# -_-V1_5.net
KiCad netlist of a schematic drawn in Altium Designer
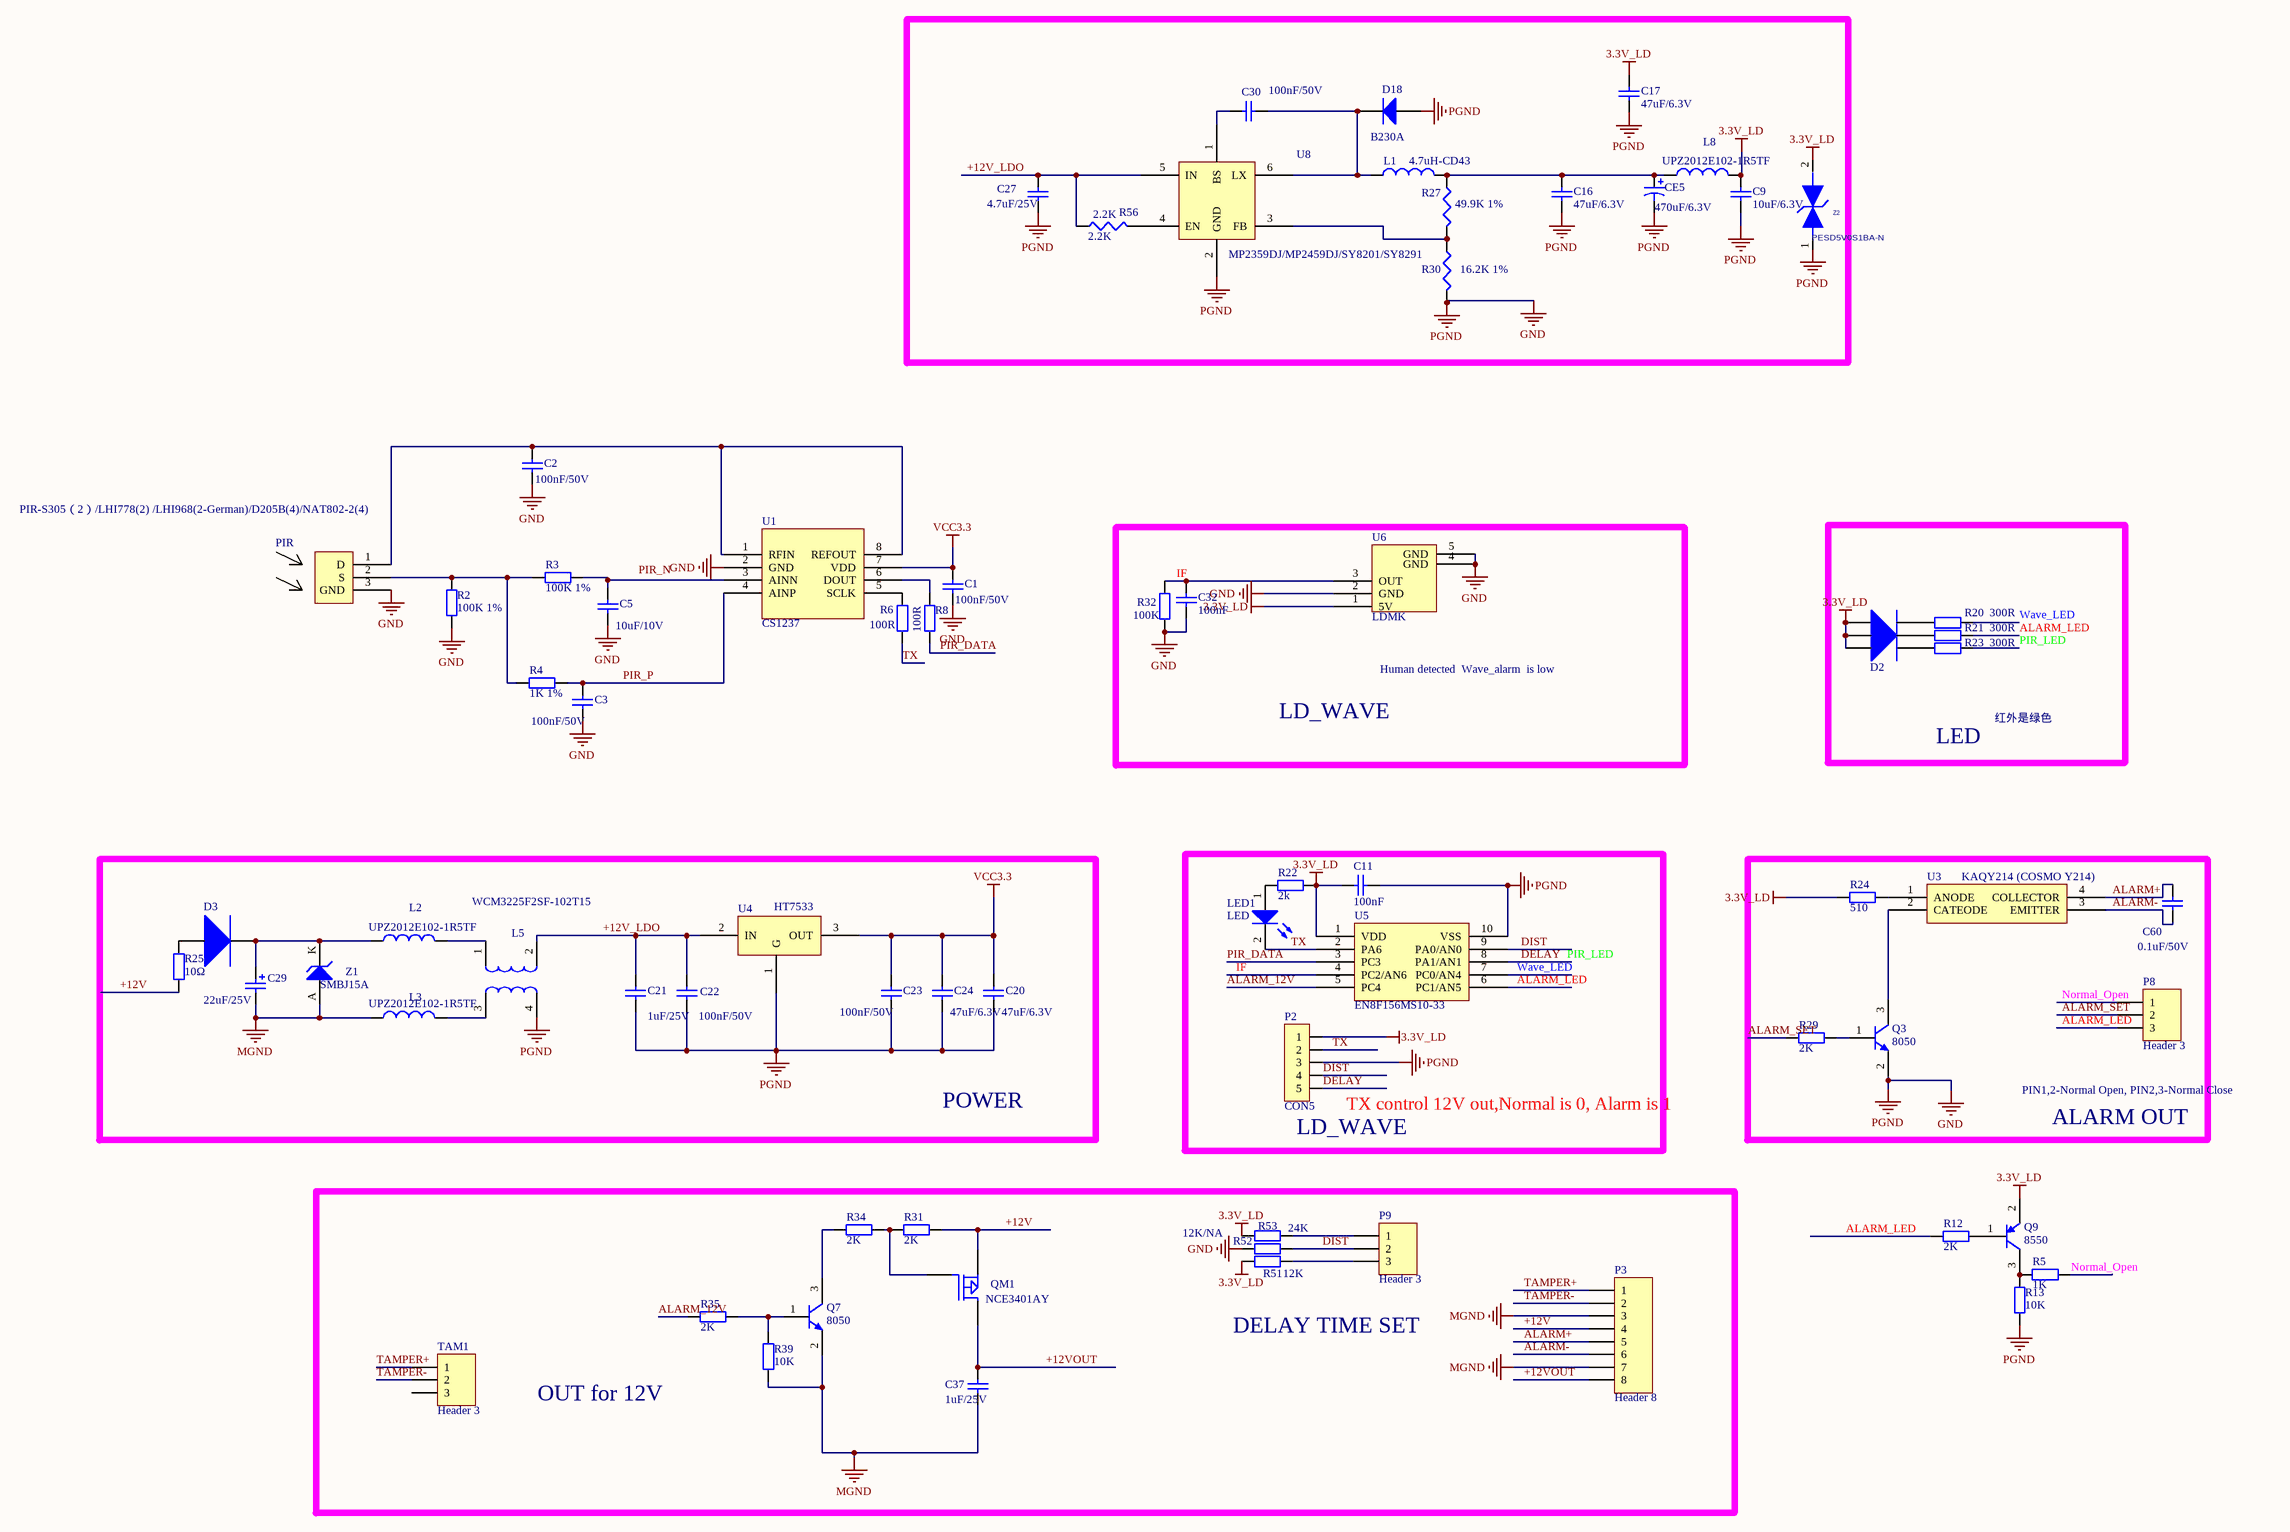
[diagram p0: 美安微波红外-芯海-V1.5.SCHDOC]

(export (version "E")
  (design (tool "Eeschema 10.0.6"))
  (components
    (comp (ref "C1")
      (value "100nF/50V")
      (footprint "0603")
      (description "Capacitor")
      (fields (field (name "PUBLISHER") "Altium Limited"))
      (libsource (lib "Miscellaneous Devices") (part "Cap"))
    )
    (comp (ref "C2")
      (value "100nF/50V")
      (footprint "0603")
      (description "Capacitor")
      (fields (field (name "PUBLISHER") "Altium Limited"))
      (libsource (lib "Miscellaneous Devices") (part "Cap"))
    )
    (comp (ref "C3")
      (value "100nF/50V")
      (footprint "0603")
      (description "Capacitor")
      (fields (field (name "PUBLISHER") "Altium Limited"))
      (libsource (lib "Miscellaneous Devices") (part "Cap"))
    )
    (comp (ref "C5")
      (value "10uF/10V")
      (footprint "C0805")
      (description "Capacitor")
      (fields (field (name "PUBLISHER") "Altium Limited"))
      (libsource (lib "Miscellaneous Devices") (part "Cap"))
    )
    (comp (ref "C9")
      (value "10uF/6.3V")
      (footprint "0603")
      (description "Capacitor")
      (fields (field (name "PUBLISHER") "Altium Limited"))
      (libsource (lib "Miscellaneous Devices") (part "Cap"))
    )
    (comp (ref "C11")
      (value "100nF")
      (footprint "0603")
      (description "Capacitor")
      (fields (field (name "PUBLISHER") "Altium Limited"))
      (libsource (lib "Miscellaneous Devices") (part "Cap"))
    )
    (comp (ref "C16")
      (value "47uF/6.3V")
      (footprint "0805")
      (description "Capacitor (Semiconductor SIM Model)")
      (fields (field (name "PUBLISHER") "Altium Limited"))
      (libsource (lib "Miscellaneous Devices") (part "Cap Semi"))
    )
    (comp (ref "C17")
      (value "47uF/6.3V")
      (footprint "0805")
      (description "Capacitor (Semiconductor SIM Model)")
      (fields (field (name "PUBLISHER") "Altium Limited"))
      (libsource (lib "Miscellaneous Devices") (part "Cap Semi"))
    )
    (comp (ref "C20")
      (value "47uF/6.3V")
      (footprint "C0805")
      (description "Capacitor")
      (fields (field (name "PUBLISHER") "Altium Limited"))
      (libsource (lib "Miscellaneous Devices") (part "Cap"))
    )
    (comp (ref "C21")
      (value "1uF/25V")
      (footprint "C0805")
      (description "Capacitor")
      (fields (field (name "PUBLISHER") "Altium Limited"))
      (libsource (lib "Miscellaneous Devices") (part "Cap"))
    )
    (comp (ref "C22")
      (value "100nF/50V")
      (footprint "C0603")
      (description "Capacitor")
      (fields (field (name "PUBLISHER") "Altium Limited"))
      (libsource (lib "Miscellaneous Devices") (part "Cap"))
    )
    (comp (ref "C23")
      (value "100nF/50V")
      (footprint "C0603")
      (description "Capacitor")
      (fields (field (name "PUBLISHER") "Altium Limited"))
      (libsource (lib "Miscellaneous Devices") (part "Cap"))
    )
    (comp (ref "C24")
      (value "47uF/6.3V")
      (footprint "C0805")
      (description "Capacitor")
      (fields (field (name "PUBLISHER") "Altium Limited"))
      (libsource (lib "Miscellaneous Devices") (part "Cap"))
    )
    (comp (ref "C27")
      (value "4.7uF/25V")
      (footprint "0805")
      (description "Capacitor (Semiconductor SIM Model)")
      (fields (field (name "PUBLISHER") "Altium Limited"))
      (libsource (lib "Miscellaneous Devices") (part "Cap Semi"))
    )
    (comp (ref "C29")
      (value "22uF/25V")
      (footprint "CAP5.0X5.4")
      (description "Polarized Capacitor (Axial)")
      (fields (field (name "PUBLISHER") "Altium Limited"))
      (libsource (lib "Miscellaneous Devices") (part "Cap Pol2"))
    )
    (comp (ref "C30")
      (value "100nF/50V")
      (footprint "0603")
      (description "Capacitor (Semiconductor SIM Model)")
      (fields (field (name "PUBLISHER") "Altium Limited"))
      (libsource (lib "Miscellaneous Devices") (part "Cap Semi"))
    )
    (comp (ref "C32")
      (value "100nF")
      (footprint "0603")
      (description "Capacitor")
      (fields (field (name "PUBLISHER") "Altium Limited"))
      (libsource (lib "Miscellaneous Devices") (part "Cap"))
    )
    (comp (ref "C37")
      (value "1uF/25V")
      (footprint "C0805")
      (description "Capacitor")
      (fields (field (name "PUBLISHER") "Altium Limited"))
      (libsource (lib "Miscellaneous Devices") (part "Cap"))
    )
    (comp (ref "C60")
      (value "0.1uF/50V")
      (footprint "C0603")
      (description "Capacitor")
      (fields (field (name "PUBLISHER") "Altium Limited"))
      (libsource (lib "Miscellaneous Devices") (part "Cap"))
    )
    (comp (ref "CE5")
      (value "470uF/6.3V")
      (footprint "CAP6.3X5.4")
      (description "Polarized Capacitor (Radial)")
      (fields (field (name "PUBLISHER") "Altium Limited"))
      (libsource (lib "Miscellaneous Devices") (part "Cap Pol1"))
    )
    (comp (ref "D2") (value "led三色共阴极灯") (footprint "三色灯") (libsource (lib "微波红外双鉴电路") (part "led三色共阴极灯")))
    (comp (ref "D3") (value "SS14") (footprint "SS14") (libsource (lib "微波红外双鉴电路") (part "SS14")))
    (comp (ref "D18")
      (value "B230A")
      (footprint "SMA")
      (description "1 Amp General Purpose Rectifier")
      (fields (field (name "PUBLISHER") "Altium Limited"))
      (libsource (lib "Miscellaneous Devices") (part "Diode 1N4007"))
    )
    (comp (ref "L1")
      (value "4.7uH-CD43")
      (footprint "CDRH3D16")
      (description "Inductor")
      (fields (field (name "PUBLISHER") "Altium Limited"))
      (libsource (lib "") (part "Inductor_1"))
    )
    (comp (ref "L2")
      (value "UPZ2012E102-1R5TF")
      (footprint "R0805")
      (description "Inductor")
      (fields (field (name "PUBLISHER") "Altium Limited"))
      (libsource (lib "Miscellaneous Devices") (part "Inductor"))
    )
    (comp (ref "L3")
      (value "UPZ2012E102-1R5TF")
      (footprint "R0805")
      (description "Inductor")
      (fields (field (name "PUBLISHER") "Altium Limited"))
      (libsource (lib "Miscellaneous Devices") (part "Inductor"))
    )
    (comp (ref "L5")
      (value "WCM3225F2SF-102T15")
      (footprint "CMC-3225")
      (description "Transformer")
      (fields (field (name "PUBLISHER") "Altium Limited"))
      (libsource (lib "Miscellaneous Devices") (part "Trans"))
    )
    (comp (ref "L8")
      (value "UPZ2012E102-1R5TF")
      (footprint "R0805")
      (description "Inductor")
      (fields (field (name "PUBLISHER") "Altium Limited"))
      (libsource (lib "Miscellaneous Devices") (part "Inductor"))
    )
    (comp (ref "LED1")
      (value "LED")
      (footprint "LED-0603")
      (fields (field (name "PUBLISHER") "Altium Limited"))
      (libsource (lib "Miscellaneous Devices") (part "LED0"))
    )
    (comp (ref "P2")
      (value "CON5")
      (footprint "PH2.0-5P")
      (description "Connector")
      (libsource (lib "*") (part "CON5"))
    )
    (comp (ref "P3")
      (value "Header 8")
      (footprint "5.08dip-8")
      (description "Header, 8-Pin")
      (fields (field (name "PUBLISHER") "Altium Limited"))
      (libsource (lib "Miscellaneous Connectors") (part "Header 8"))
    )
    (comp (ref "P8")
      (value "Header 3")
      (footprint "HDR1X3")
      (description "Header, 3-Pin")
      (fields (field (name "PUBLISHER") "Altium Limited"))
      (libsource (lib "Miscellaneous Connectors") (part "Header 3"))
    )
    (comp (ref "P9")
      (value "Header 3")
      (footprint "HDR1X3")
      (description "Header, 3-Pin")
      (fields (field (name "PUBLISHER") "Altium Limited"))
      (libsource (lib "Miscellaneous Connectors") (part "Header 3"))
    )
    (comp (ref "PIR")
      (value "PIR-S305（2）/LHI778(2) /LHI968(2-German)/D205B(4)/NAT802-2(4)")
      (footprint "pir3")
      (libsource (lib "安防") (part "PIR"))
    )
    (comp (ref "Q3")
      (value "8050")
      (footprint "8050&8550")
      (description "NPN General Purpose Amplifier")
      (fields (field (name "PUBLISHER") "Altium Limited"))
      (libsource (lib "圆形报警器NEW-V2.0") (part "2N3904"))
    )
    (comp (ref "Q7")
      (value "8050")
      (footprint "8050&8550")
      (description "NPN General Purpose Amplifier")
      (fields (field (name "PUBLISHER") "Altium Limited"))
      (libsource (lib "圆形报警器NEW-V2.0") (part "2N3904"))
    )
    (comp (ref "Q9")
      (value "8550")
      (footprint "8050&8550")
      (description "PNP General Purpose Amplifier")
      (fields (field (name "PUBLISHER") "Altium Limited"))
      (libsource (lib "圆形报警器NEW-V2.0") (part "2N3906"))
    )
    (comp (ref "QM1") (value "NCE3401AY") (footprint "SOT-23") (libsource (lib "*") (part "MOSFET P")))
    (comp (ref "R2")
      (value "100K 1%")
      (footprint "R0603")
      (description "Resistor")
      (fields (field (name "PUBLISHER") "Altium Limited"))
      (libsource (lib "Miscellaneous Devices") (part "Res2"))
    )
    (comp (ref "R3")
      (value "100K 1%")
      (footprint "R0603")
      (description "Resistor")
      (fields (field (name "PUBLISHER") "Altium Limited"))
      (libsource (lib "") (part "Res2_3"))
    )
    (comp (ref "R4")
      (value "1K 1%")
      (footprint "R0603")
      (description "Resistor")
      (fields (field (name "PUBLISHER") "Altium Limited"))
      (libsource (lib "") (part "Res2_3"))
    )
    (comp (ref "R5")
      (value "1K")
      (footprint "R0603")
      (description "Resistor")
      (fields (field (name "PUBLISHER") "Altium Limited"))
      (libsource (lib "") (part "Res2_2"))
    )
    (comp (ref "R6")
      (value "100R")
      (footprint "R0603")
      (description "Resistor")
      (fields (field (name "PUBLISHER") "Altium Limited"))
      (libsource (lib "") (part "Res2_1"))
    )
    (comp (ref "R8")
      (value "100R")
      (footprint "R0603")
      (description "Resistor")
      (fields (field (name "PUBLISHER") "Altium Limited"))
      (libsource (lib "") (part "Res2_1"))
    )
    (comp (ref "R12")
      (value "2K")
      (footprint "R0603")
      (description "Resistor")
      (fields (field (name "PUBLISHER") "Altium Limited"))
      (libsource (lib "") (part "Res2_3"))
    )
    (comp (ref "R13")
      (value "10K")
      (footprint "R0603")
      (description "Resistor")
      (fields (field (name "PUBLISHER") "Altium Limited"))
      (libsource (lib "") (part "Res2_1"))
    )
    (comp (ref "R20")
      (value "300R")
      (footprint "R0603")
      (description "Resistor")
      (fields (field (name "Comment") "Res2") (field (name "PUBLISHER") "Altium Limited"))
      (libsource (lib "") (part "Res2_3"))
    )
    (comp (ref "R21")
      (value "300R")
      (footprint "R0603")
      (description "Resistor")
      (fields (field (name "Comment") "Res2") (field (name "PUBLISHER") "Altium Limited"))
      (libsource (lib "") (part "Res2_3"))
    )
    (comp (ref "R22")
      (value "2k")
      (footprint "R0603")
      (description "Resistor")
      (fields (field (name "Comment") "Res2") (field (name "PUBLISHER") "Altium Limited"))
      (libsource (lib "") (part "Res2_3"))
    )
    (comp (ref "R23")
      (value "300R")
      (footprint "R0603")
      (description "Resistor")
      (fields (field (name "Comment") "Res2") (field (name "PUBLISHER") "Altium Limited"))
      (libsource (lib "") (part "Res2_3"))
    )
    (comp (ref "R24")
      (value "510")
      (footprint "R0603")
      (description "Resistor")
      (fields (field (name "PUBLISHER") "Altium Limited"))
      (libsource (lib "") (part "Res2_3"))
    )
    (comp (ref "R25")
      (value "10Ω")
      (footprint "C0805")
      (description "Resistor")
      (fields (field (name "PUBLISHER") "Altium Limited"))
      (libsource (lib "") (part "Res2_1"))
    )
    (comp (ref "R27")
      (value "49.9K 1%")
      (footprint "0603")
      (description "Resistor")
      (fields (field (name "PUBLISHER") "Altium Limited"))
      (libsource (lib "Miscellaneous Devices") (part "Res3"))
    )
    (comp (ref "R29")
      (value "2K")
      (footprint "R0603")
      (description "Resistor")
      (fields (field (name "PUBLISHER") "Altium Limited"))
      (libsource (lib "") (part "Res2_2"))
    )
    (comp (ref "R30")
      (value "16.2K 1%")
      (footprint "0603")
      (description "Resistor")
      (fields (field (name "PUBLISHER") "Altium Limited"))
      (libsource (lib "Miscellaneous Devices") (part "Res3"))
    )
    (comp (ref "R31")
      (value "2K")
      (footprint "R0603")
      (description "Resistor")
      (fields (field (name "PUBLISHER") "Altium Limited"))
      (libsource (lib "") (part "Res2_2"))
    )
    (comp (ref "R32")
      (value "100K")
      (footprint "R0603")
      (description "Resistor")
      (fields (field (name "PUBLISHER") "Altium Limited"))
      (libsource (lib "Miscellaneous Devices") (part "Res2"))
    )
    (comp (ref "R34")
      (value "2K")
      (footprint "R0603")
      (description "Resistor")
      (fields (field (name "PUBLISHER") "Altium Limited"))
      (libsource (lib "") (part "Res2_2"))
    )
    (comp (ref "R35")
      (value "2K")
      (footprint "R0603")
      (description "Resistor")
      (fields (field (name "PUBLISHER") "Altium Limited"))
      (libsource (lib "") (part "Res2_2"))
    )
    (comp (ref "R39")
      (value "10K")
      (footprint "R0603")
      (description "Resistor")
      (fields (field (name "PUBLISHER") "Altium Limited"))
      (libsource (lib "Miscellaneous Devices") (part "Res2"))
    )
    (comp (ref "R51")
      (value "12K")
      (footprint "R0603")
      (description "Resistor")
      (fields (field (name "PUBLISHER") "Altium Limited"))
      (libsource (lib "*") (part "Res2"))
    )
    (comp (ref "R52")
      (value "12K/NA")
      (footprint "R0603")
      (description "Resistor")
      (fields (field (name "PUBLISHER") "Altium Limited"))
      (libsource (lib "*") (part "Res2"))
    )
    (comp (ref "R53")
      (value "24K")
      (footprint "R0603")
      (description "Resistor")
      (fields (field (name "PUBLISHER") "Altium Limited"))
      (libsource (lib "*") (part "Res2"))
    )
    (comp (ref "R56")
      (value "2.2K")
      (footprint "0603")
      (description "Resistor")
      (fields (field (name "ALTIUM_VALUE") "2.2K") (field (name "PUBLISHER") "Altium Limited"))
      (libsource (lib "Miscellaneous Devices") (part "Res3"))
    )
    (comp (ref "TAM1")
      (value "Header 3")
      (footprint "KW12")
      (description "Header, 3-Pin")
      (fields (field (name "PUBLISHER") "Altium Limited"))
      (libsource (lib "Miscellaneous Connectors") (part "Header 3"))
    )
    (comp (ref "U1") (value "CS1237") (footprint "SOP_8") (libsource (lib "美安微波红外-芯海-V0.1") (part "CS1237")))
    (comp (ref "U3")
      (value "KAQY214 (COSMO Y214)")
      (footprint "TLP627")
      (fields (field (name "Comment") "TLP627"))
      (libsource (lib "微波红外双鉴电路") (part "TLP627"))
    )
    (comp (ref "U4") (value "HT7533") (footprint "SOT-89") (libsource (lib "MYLIB") (part "12S33")))
    (comp (ref "U5")
      (value "EN8F156MS10-33")
      (footprint "My Footprint View:MSOP10-0.5")
      (libsource (lib "Schlib1") (part "EN8F156MS10-33"))
    )
    (comp (ref "U6")
      (value "LDMK")
      (footprint "LDMK")
      (libsource (lib "BD-SY-NOPOWER-TS01S-V1.0") (part "LDMK"))
    )
    (comp (ref "U8")
      (value "MP2359DJ/MP2459DJ/SY8201/SY8291")
      (footprint "SOT23-6")
      (libsource (lib "SPECIAL-L-V6.6") (part "SY8120B"))
    )
    (comp (ref "Z1")
      (value "SMBJ15A")
      (footprint "SMB")
      (description "Zener Diode")
      (fields (field (name "PUBLISHER") "Altium Limited"))
      (libsource (lib "Miscellaneous Devices") (part "D Zener"))
    )
    (comp (ref "Z2")
      (value "PESD5V0S1BA-N")
      (footprint "SOD-323")
      (description "VBR=5.780V@1mA;VRWM=3.5V@IRWM=0.5uA;Ct=30pF")
      (fields
        (field (name "MFR") "NXP")
        (field (name "MPN") "RSB6.8CS//VMNZ6.8CST2R  //PESD5V0S1BL//ESDALC6V1-1BM2//ESD9B5.0ST5G//VMNZ6.8CSGJT2R//RSB6.8CM")
      )
      (libsource (lib "*") (part "ESD-PESD5V0S1BL-VMN2"))
    )
  )
  (nets
    (net (code "1") (name "/+12V") (class "Default")
      (node (ref "P3") (pin "4") (pinfunction "4_4") (pintype "passive"))
      (node (ref "QM1") (pin "2") (pinfunction "S_2") (pintype "passive"))
      (node (ref "R25") (pin "2") (pinfunction "2_2") (pintype "passive"))
      (node (ref "R31") (pin "2") (pinfunction "2_2") (pintype "passive"))
    )
    (net (code "2") (name "/+12VOUT") (class "Default")
      (node (ref "C37") (pin "2") (pinfunction "2_2") (pintype "passive"))
      (node (ref "P3") (pin "8") (pinfunction "8_8") (pintype "passive"))
      (node (ref "QM1") (pin "3") (pinfunction "D_3") (pintype "passive"))
    )
    (net (code "3") (name "/+12V_LDO") (class "Default")
      (node (ref "C21") (pin "2") (pinfunction "2_2") (pintype "passive"))
      (node (ref "C22") (pin "2") (pinfunction "2_2") (pintype "passive"))
      (node (ref "C27") (pin "1") (pinfunction "1_1") (pintype "passive"))
      (node (ref "L5") (pin "2") (pinfunction "2_2") (pintype "passive"))
      (node (ref "R56") (pin "1") (pinfunction "1_1") (pintype "passive"))
      (node (ref "U4") (pin "2") (pinfunction "IN_2") (pintype "passive"))
      (node (ref "U8") (pin "5") (pinfunction "IN_5") (pintype "passive"))
    )
    (net (code "4") (name "/ALARM+") (class "Default")
      (node (ref "C60") (pin "2") (pinfunction "2_2") (pintype "passive"))
      (node (ref "P3") (pin "5") (pinfunction "5_5") (pintype "passive"))
      (node (ref "U3") (pin "4") (pinfunction "COLLECTOR_4") (pintype "passive"))
    )
    (net (code "5") (name "/ALARM-") (class "Default")
      (node (ref "C60") (pin "1") (pinfunction "1_1") (pintype "passive"))
      (node (ref "P3") (pin "6") (pinfunction "6_6") (pintype "passive"))
      (node (ref "U3") (pin "3") (pinfunction "EMITTER_3") (pintype "passive"))
    )
    (net (code "6") (name "/ALARM_12V") (class "Default")
      (node (ref "R35") (pin "1") (pinfunction "1_1") (pintype "passive"))
      (node (ref "U5") (pin "5") (pinfunction "PC4_5") (pintype "passive"))
    )
    (net (code "7") (name "/ALARM_LED") (class "Default")
      (node (ref "P8") (pin "3") (pinfunction "3_3") (pintype "passive"))
      (node (ref "R12") (pin "2") (pinfunction "2_2") (pintype "passive"))
      (node (ref "R21") (pin "1") (pinfunction "1_1") (pintype "passive"))
      (node (ref "U5") (pin "6") (pinfunction "PC1/AN5_6") (pintype "passive"))
    )
    (net (code "8") (name "/ALARM_SET") (class "Default")
      (node (ref "P8") (pin "2") (pinfunction "2_2") (pintype "passive"))
      (node (ref "R29") (pin "1") (pinfunction "1_1") (pintype "passive"))
    )
    (net (code "9") (name "/DELAY") (class "Default")
      (node (ref "P2") (pin "5") (pinfunction "5_5") (pintype "passive"))
      (node (ref "R23") (pin "1") (pinfunction "1_1") (pintype "passive"))
      (node (ref "U5") (pin "8") (pinfunction "PA1/AN1_8") (pintype "passive"))
    )
    (net (code "10") (name "/DIST") (class "Default")
      (node (ref "P2") (pin "4") (pinfunction "4_4") (pintype "passive"))
      (node (ref "P9") (pin "2") (pinfunction "2_2") (pintype "passive"))
      (node (ref "R52") (pin "1") (pinfunction "1_1") (pintype "passive"))
      (node (ref "U5") (pin "9") (pinfunction "PA0/AN0_9") (pintype "passive"))
    )
    (net (code "11") (name "/IF") (class "Default")
      (node (ref "C32") (pin "2") (pinfunction "2_2") (pintype "passive"))
      (node (ref "R32") (pin "2") (pinfunction "2_2") (pintype "passive"))
      (node (ref "U5") (pin "4") (pinfunction "PC2/AN6_4") (pintype "passive"))
      (node (ref "U6") (pin "3") (pinfunction "OUT_3") (pintype "passive"))
    )
    (net (code "12") (name "/Normal_Open") (class "Default")
      (node (ref "P8") (pin "1") (pinfunction "1_1") (pintype "passive"))
      (node (ref "R5") (pin "2") (pinfunction "2_2") (pintype "passive"))
    )
    (net (code "13") (name "/PIR_DATA") (class "Default")
      (node (ref "R8") (pin "2") (pinfunction "2_2") (pintype "passive"))
      (node (ref "U5") (pin "3") (pinfunction "PC3_3") (pintype "passive"))
    )
    (net (code "15") (name "/PIR_P") (class "Default")
      (node (ref "C3") (pin "2") (pinfunction "2_2") (pintype "passive"))
      (node (ref "R4") (pin "1") (pinfunction "1_1") (pintype "passive"))
      (node (ref "U1") (pin "4") (pinfunction "AINP_4") (pintype "passive"))
    )
    (net (code "16") (name "/TAMPER+") (class "Default")
      (node (ref "P3") (pin "1") (pinfunction "1_1") (pintype "passive"))
      (node (ref "TAM1") (pin "1") (pinfunction "1_1") (pintype "passive"))
    )
    (net (code "17") (name "/TAMPER-") (class "Default")
      (node (ref "P3") (pin "2") (pinfunction "2_2") (pintype "passive"))
      (node (ref "TAM1") (pin "2") (pinfunction "2_2") (pintype "passive"))
    )
    (net (code "18") (name "/TX") (class "Default")
      (node (ref "LED1") (pin "2") (pinfunction "K_2") (pintype "passive"))
      (node (ref "P2") (pin "2") (pinfunction "2_2") (pintype "passive"))
      (node (ref "R6") (pin "2") (pinfunction "2_2") (pintype "passive"))
      (node (ref "U5") (pin "2") (pinfunction "PA6_2") (pintype "passive"))
    )
    (net (code "20") (name "/Wave_LED") (class "Default")
      (node (ref "R20") (pin "1") (pinfunction "1_1") (pintype "passive"))
      (node (ref "U5") (pin "7") (pinfunction "PC0/AN4_7") (pintype "passive"))
    )
    (net (code "21") (name "3.3V_LD") (class "Default")
      (node (ref "C11") (pin "2") (pinfunction "2_2") (pintype "passive"))
      (node (ref "C17") (pin "1") (pinfunction "1_1") (pintype "passive"))
      (node (ref "C9") (pin "1") (pinfunction "1_1") (pintype "passive"))
      (node (ref "D2") (pin "1") (pinfunction "A+_1") (pintype "passive"))
      (node (ref "D2") (pin "2") (pinfunction "B+_2") (pintype "passive"))
      (node (ref "D2") (pin "3") (pinfunction "C+_3") (pintype "passive"))
      (node (ref "L8") (pin "1") (pinfunction "1_1") (pintype "passive"))
      (node (ref "P2") (pin "1") (pinfunction "1_1") (pintype "passive"))
      (node (ref "Q9") (pin "2") (pinfunction "E_2") (pintype "passive"))
      (node (ref "R22") (pin "1") (pinfunction "1_1") (pintype "passive"))
      (node (ref "R24") (pin "2") (pinfunction "2_2") (pintype "passive"))
      (node (ref "R51") (pin "2") (pinfunction "2_2") (pintype "passive"))
      (node (ref "R53") (pin "2") (pinfunction "2_2") (pintype "passive"))
      (node (ref "U5") (pin "1") (pinfunction "VDD_1") (pintype "passive"))
      (node (ref "U6") (pin "1") (pinfunction "5V_1") (pintype "passive"))
      (node (ref "Z2") (pin "2") (pinfunction "2_2") (pintype "passive"))
    )
    (net (code "22") (name "GND") (class "Default")
      (node (ref "C1") (pin "1") (pinfunction "1_1") (pintype "passive"))
      (node (ref "C11") (pin "1") (pinfunction "1_1") (pintype "passive"))
      (node (ref "C16") (pin "2") (pinfunction "2_2") (pintype "passive"))
      (node (ref "C17") (pin "2") (pinfunction "2_2") (pintype "passive"))
      (node (ref "C2") (pin "1") (pinfunction "1_1") (pintype "passive"))
      (node (ref "C20") (pin "1") (pinfunction "1_1") (pintype "passive"))
      (node (ref "C21") (pin "1") (pinfunction "1_1") (pintype "passive"))
      (node (ref "C22") (pin "1") (pinfunction "1_1") (pintype "passive"))
      (node (ref "C23") (pin "1") (pinfunction "1_1") (pintype "passive"))
      (node (ref "C24") (pin "1") (pinfunction "1_1") (pintype "passive"))
      (node (ref "C27") (pin "2") (pinfunction "2_2") (pintype "passive"))
      (node (ref "C3") (pin "1") (pinfunction "1_1") (pintype "passive"))
      (node (ref "C32") (pin "1") (pinfunction "1_1") (pintype "passive"))
      (node (ref "C5") (pin "1") (pinfunction "1_1") (pintype "passive"))
      (node (ref "C9") (pin "2") (pinfunction "2_2") (pintype "passive"))
      (node (ref "CE5") (pin "2") (pinfunction "2_2") (pintype "passive"))
      (node (ref "D18") (pin "1") (pinfunction "A_1") (pintype "passive"))
      (node (ref "L5") (pin "4") (pinfunction "4_4") (pintype "passive"))
      (node (ref "P2") (pin "3") (pinfunction "3_3") (pintype "passive"))
      (node (ref "PIR") (pin "3") (pinfunction "GND_3") (pintype "passive"))
      (node (ref "Q3") (pin "2") (pinfunction "E_2") (pintype "passive"))
      (node (ref "R13") (pin "2") (pinfunction "2_2") (pintype "passive"))
      (node (ref "R2") (pin "1") (pinfunction "1_1") (pintype "passive"))
      (node (ref "R30") (pin "2") (pinfunction "2_2") (pintype "passive"))
      (node (ref "R32") (pin "1") (pinfunction "1_1") (pintype "passive"))
      (node (ref "R52") (pin "2") (pinfunction "2_2") (pintype "passive"))
      (node (ref "U1") (pin "2") (pinfunction "GND_2") (pintype "passive"))
      (node (ref "U4") (pin "1") (pinfunction "G_1") (pintype "passive"))
      (node (ref "U5") (pin "10") (pinfunction "VSS_10") (pintype "passive"))
      (node (ref "U6") (pin "2") (pinfunction "GND_2") (pintype "passive"))
      (node (ref "U6") (pin "4") (pinfunction "GND_4") (pintype "passive"))
      (node (ref "U6") (pin "5") (pinfunction "GND_5") (pintype "passive"))
      (node (ref "U8") (pin "2") (pinfunction "GND_2") (pintype "passive"))
      (node (ref "Z2") (pin "1") (pinfunction "1_1") (pintype "passive"))
    )
    (net (code "23") (name "MGND") (class "Default")
      (node (ref "C29") (pin "2") (pinfunction "2_2") (pintype "passive"))
      (node (ref "C37") (pin "1") (pinfunction "1_1") (pintype "passive"))
      (node (ref "L3") (pin "2") (pinfunction "2_2") (pintype "passive"))
      (node (ref "P3") (pin "3") (pinfunction "3_3") (pintype "passive"))
      (node (ref "P3") (pin "7") (pinfunction "7_7") (pintype "passive"))
      (node (ref "Q7") (pin "2") (pinfunction "E_2") (pintype "passive"))
      (node (ref "R39") (pin "1") (pinfunction "1_1") (pintype "passive"))
      (node (ref "Z1") (pin "A") (pinfunction "A_A") (pintype "passive"))
    )
    (net (code "24") (name "Net-(C16-Pad1)") (class "Default")
      (node (ref "C16") (pin "1") (pinfunction "1_1") (pintype "passive"))
      (node (ref "CE5") (pin "1") (pinfunction "1_1") (pintype "passive"))
      (node (ref "L1") (pin "2") (pinfunction "2_2") (pintype "passive"))
      (node (ref "L8") (pin "2") (pinfunction "2_2") (pintype "passive"))
      (node (ref "R27") (pin "1") (pinfunction "1_1") (pintype "passive"))
    )
    (net (code "25") (name "Net-(D2-A-)") (class "Default")
      (node (ref "D2") (pin "4") (pinfunction "A-_4") (pintype "passive"))
      (node (ref "R20") (pin "2") (pinfunction "2_2") (pintype "passive"))
    )
    (net (code "26") (name "Net-(D2-B-)") (class "Default")
      (node (ref "D2") (pin "5") (pinfunction "B-_5") (pintype "passive"))
      (node (ref "R21") (pin "2") (pinfunction "2_2") (pintype "passive"))
    )
    (net (code "27") (name "Net-(D2-C-)") (class "Default")
      (node (ref "D2") (pin "6") (pinfunction "C-_6") (pintype "passive"))
      (node (ref "R23") (pin "2") (pinfunction "2_2") (pintype "passive"))
    )
    (net (code "28") (name "Net-(D3-B)") (class "Default")
      (node (ref "D3") (pin "1") (pinfunction "B_1") (pintype "passive"))
      (node (ref "R25") (pin "1") (pinfunction "1_1") (pintype "passive"))
    )
    (net (code "29") (name "Net-(D3-C)") (class "Default")
      (node (ref "C29") (pin "1") (pinfunction "1_1") (pintype "passive"))
      (node (ref "D3") (pin "2") (pinfunction "C_2") (pintype "passive"))
      (node (ref "L2") (pin "2") (pinfunction "2_2") (pintype "passive"))
      (node (ref "Z1") (pin "K") (pinfunction "K_K") (pintype "passive"))
    )
    (net (code "30") (name "Net-(D18-K)") (class "Default")
      (node (ref "C30") (pin "1") (pinfunction "1_1") (pintype "passive"))
      (node (ref "D18") (pin "2") (pinfunction "K_2") (pintype "passive"))
      (node (ref "L1") (pin "1") (pinfunction "1_1") (pintype "passive"))
      (node (ref "U8") (pin "6") (pinfunction "LX_6") (pintype "passive"))
    )
    (net (code "31") (name "Net-(L2-Pad1)") (class "Default")
      (node (ref "L2") (pin "1") (pinfunction "1_1") (pintype "passive"))
      (node (ref "L5") (pin "1") (pinfunction "1_1") (pintype "passive"))
    )
    (net (code "32") (name "Net-(L3-Pad1)") (class "Default")
      (node (ref "L3") (pin "1") (pinfunction "1_1") (pintype "passive"))
      (node (ref "L5") (pin "3") (pinfunction "3_3") (pintype "passive"))
    )
    (net (code "33") (name "Net-(LED1-A)") (class "Default")
      (node (ref "LED1") (pin "1") (pinfunction "A_1") (pintype "passive"))
      (node (ref "R22") (pin "2") (pinfunction "2_2") (pintype "passive"))
    )
    (net (code "34") (name "Net-(P9-Pad1)") (class "Default")
      (node (ref "P9") (pin "1") (pinfunction "1_1") (pintype "passive"))
      (node (ref "R53") (pin "1") (pinfunction "1_1") (pintype "passive"))
    )
    (net (code "35") (name "Net-(P9-Pad3)") (class "Default")
      (node (ref "P9") (pin "3") (pinfunction "3_3") (pintype "passive"))
      (node (ref "R51") (pin "1") (pinfunction "1_1") (pintype "passive"))
    )
    (net (code "36") (name "Net-(PIR-D)") (class "Default")
      (node (ref "C2") (pin "2") (pinfunction "2_2") (pintype "passive"))
      (node (ref "PIR") (pin "1") (pinfunction "D_1") (pintype "passive"))
      (node (ref "U1") (pin "1") (pinfunction "RFIN_1") (pintype "passive"))
      (node (ref "U1") (pin "8") (pinfunction "REFOUT_8") (pintype "passive"))
    )
    (net (code "37") (name "Net-(PIR-S)") (class "Default")
      (node (ref "PIR") (pin "2") (pinfunction "S_2") (pintype "passive"))
      (node (ref "R2") (pin "2") (pinfunction "2_2") (pintype "passive"))
      (node (ref "R3") (pin "2") (pinfunction "2_2") (pintype "passive"))
      (node (ref "R4") (pin "2") (pinfunction "2_2") (pintype "passive"))
    )
    (net (code "38") (name "Net-(Q3-B)") (class "Default")
      (node (ref "Q3") (pin "1") (pinfunction "B_1") (pintype "passive"))
      (node (ref "R29") (pin "2") (pinfunction "2_2") (pintype "passive"))
    )
    (net (code "39") (name "Net-(Q3-C)") (class "Default")
      (node (ref "Q3") (pin "3") (pinfunction "C_3") (pintype "passive"))
      (node (ref "U3") (pin "2") (pinfunction "CATEODE_2") (pintype "passive"))
    )
    (net (code "40") (name "Net-(Q7-B)") (class "Default")
      (node (ref "Q7") (pin "1") (pinfunction "B_1") (pintype "passive"))
      (node (ref "R35") (pin "2") (pinfunction "2_2") (pintype "passive"))
      (node (ref "R39") (pin "2") (pinfunction "2_2") (pintype "passive"))
    )
    (net (code "41") (name "Net-(Q7-C)") (class "Default")
      (node (ref "Q7") (pin "3") (pinfunction "C_3") (pintype "passive"))
      (node (ref "R34") (pin "1") (pinfunction "1_1") (pintype "passive"))
    )
    (net (code "42") (name "Net-(Q9-B)") (class "Default")
      (node (ref "Q9") (pin "1") (pinfunction "B_1") (pintype "passive"))
      (node (ref "R12") (pin "1") (pinfunction "1_1") (pintype "passive"))
    )
    (net (code "43") (name "Net-(Q9-C)") (class "Default")
      (node (ref "Q9") (pin "3") (pinfunction "C_3") (pintype "passive"))
      (node (ref "R13") (pin "1") (pinfunction "1_1") (pintype "passive"))
      (node (ref "R5") (pin "1") (pinfunction "1_1") (pintype "passive"))
    )
    (net (code "44") (name "Net-(QM1-G)") (class "Default")
      (node (ref "QM1") (pin "1") (pinfunction "G_1") (pintype "passive"))
      (node (ref "R31") (pin "1") (pinfunction "1_1") (pintype "passive"))
      (node (ref "R34") (pin "2") (pinfunction "2_2") (pintype "passive"))
    )
    (net (code "45") (name "Net-(U1-AINN)") (class "Default")
      (node (ref "C5") (pin "2") (pinfunction "2_2") (pintype "passive"))
      (node (ref "R3") (pin "1") (pinfunction "1_1") (pintype "passive"))
      (node (ref "U1") (pin "3") (pinfunction "AINN_3") (pintype "passive"))
    )
    (net (code "46") (name "Net-(U1-DOUT)") (class "Default")
      (node (ref "R8") (pin "1") (pinfunction "1_1") (pintype "passive"))
      (node (ref "U1") (pin "6") (pinfunction "DOUT_6") (pintype "passive"))
    )
    (net (code "47") (name "Net-(U1-SCLK)") (class "Default")
      (node (ref "R6") (pin "1") (pinfunction "1_1") (pintype "passive"))
      (node (ref "U1") (pin "5") (pinfunction "SCLK_5") (pintype "passive"))
    )
    (net (code "48") (name "Net-(U3-ANODE)") (class "Default")
      (node (ref "R24") (pin "1") (pinfunction "1_1") (pintype "passive"))
      (node (ref "U3") (pin "1") (pinfunction "ANODE_1") (pintype "passive"))
    )
    (net (code "49") (name "Net-(U8-BS)") (class "Default")
      (node (ref "C30") (pin "2") (pinfunction "2_2") (pintype "passive"))
      (node (ref "U8") (pin "1") (pinfunction "BS_1") (pintype "passive"))
    )
    (net (code "50") (name "Net-(U8-EN)") (class "Default")
      (node (ref "R56") (pin "2") (pinfunction "2_2") (pintype "passive"))
      (node (ref "U8") (pin "4") (pinfunction "EN_4") (pintype "passive"))
    )
    (net (code "51") (name "Net-(U8-FB)") (class "Default")
      (node (ref "R27") (pin "2") (pinfunction "2_2") (pintype "passive"))
      (node (ref "R30") (pin "1") (pinfunction "1_1") (pintype "passive"))
      (node (ref "U8") (pin "3") (pinfunction "FB_3") (pintype "passive"))
    )
    (net (code "52") (name "VCC3.3") (class "Default")
      (node (ref "C1") (pin "2") (pinfunction "2_2") (pintype "passive"))
      (node (ref "C20") (pin "2") (pinfunction "2_2") (pintype "passive"))
      (node (ref "C23") (pin "2") (pinfunction "2_2") (pintype "passive"))
      (node (ref "C24") (pin "2") (pinfunction "2_2") (pintype "passive"))
      (node (ref "U1") (pin "7") (pinfunction "VDD_7") (pintype "passive"))
      (node (ref "U4") (pin "3") (pinfunction "OUT_3") (pintype "passive"))
    )
    (net (code "53") (name "unconnected-(TAM1-Pad3)") (class "Default")
      (node (ref "TAM1") (pin "3") (pinfunction "3_3") (pintype "passive"))
    )
  )
)
